# tx.net
KiCad netlist of a schematic drawn in EAGLE
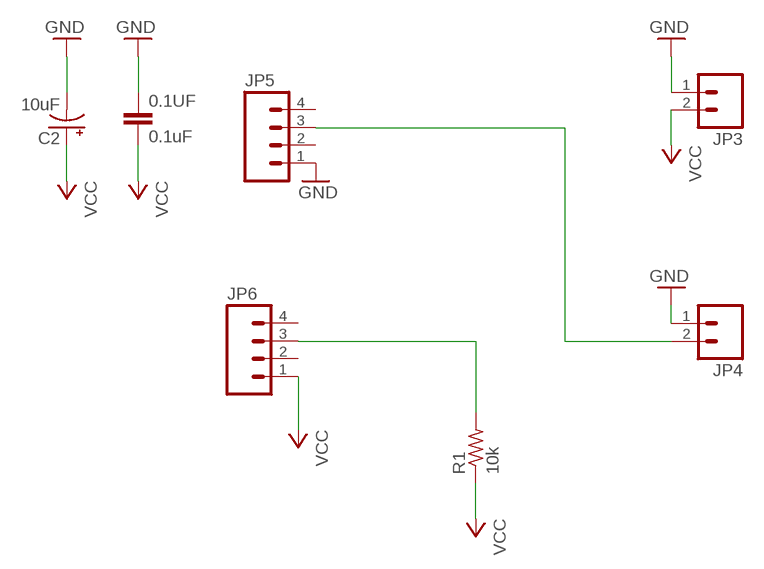
[diagram p0: schematic, sheet 1]

(export (version "E")
  (design (tool "Eeschema 10.0.6"))
  (components
    (comp (ref "0.1UF")
      (value "0.1uF")
      (footprint "eagle-import:0603-CAP")
      (libsource (lib "eagle-import") (part "0.1UF-100V-10%(0603)"))
    )
    (comp (ref "C2")
      (value "10uF")
      (footprint "eagle-import:EIA6032")
      (libsource (lib "eagle-import") (part "CAP_POL6032"))
    )
    (comp (ref "JP3")
      (value "M02PTH")
      (footprint "eagle-import:1X02")
      (libsource (lib "eagle-import") (part "M02PTH"))
    )
    (comp (ref "JP4")
      (value "M02PTH")
      (footprint "eagle-import:1X02")
      (libsource (lib "eagle-import") (part "M02PTH"))
    )
    (comp (ref "JP5")
      (value "M041X04_NO_SILK")
      (footprint "eagle-import:1X04_NO_SILK")
      (libsource (lib "eagle-import") (part "M041X04_NO_SILK"))
    )
    (comp (ref "JP6")
      (value "M041X04_NO_SILK")
      (footprint "eagle-import:1X04_NO_SILK")
      (libsource (lib "eagle-import") (part "M041X04_NO_SILK"))
    )
    (comp (ref "R1")
      (value "10k")
      (footprint "eagle-import:R0805")
      (libsource (lib "eagle-import") (part "R-US_R0805"))
    )
  )
  (nets
    (net (code "1") (name "GND") (class "Default")
      (node (ref "0.1UF") (pin "1") (pinfunction "1_1") (pintype "passive"))
      (node (ref "C2") (pin "P$2") (pinfunction "-_P$2") (pintype "passive"))
      (node (ref "JP3") (pin "1") (pinfunction "1_1") (pintype "passive"))
      (node (ref "JP4") (pin "1") (pinfunction "1_1") (pintype "passive"))
      (node (ref "JP5") (pin "1") (pinfunction "1_1") (pintype "passive"))
    )
    (net (code "2") (name "Net-(JP4-Pad2)") (class "Default")
      (node (ref "JP4") (pin "2") (pinfunction "2_2") (pintype "passive"))
      (node (ref "JP5") (pin "3") (pinfunction "3_3") (pintype "passive"))
    )
    (net (code "3") (name "Net-(JP6-Pad3)") (class "Default")
      (node (ref "JP6") (pin "3") (pinfunction "3_3") (pintype "passive"))
      (node (ref "R1") (pin "2") (pinfunction "2_2") (pintype "passive"))
    )
    (net (code "4") (name "VCC") (class "Default")
      (node (ref "0.1UF") (pin "2") (pinfunction "2_2") (pintype "passive"))
      (node (ref "C2") (pin "P$1") (pinfunction "+_P$1") (pintype "passive"))
      (node (ref "JP3") (pin "2") (pinfunction "2_2") (pintype "passive"))
      (node (ref "JP6") (pin "1") (pinfunction "1_1") (pintype "passive"))
      (node (ref "R1") (pin "1") (pinfunction "1_1") (pintype "passive"))
    )
    (net (code "5") (name "unconnected-(JP5-Pad2)") (class "Default")
      (node (ref "JP5") (pin "2") (pinfunction "2_2") (pintype "passive"))
    )
    (net (code "6") (name "unconnected-(JP5-Pad4)") (class "Default")
      (node (ref "JP5") (pin "4") (pinfunction "4_4") (pintype "passive"))
    )
    (net (code "7") (name "unconnected-(JP6-Pad2)") (class "Default")
      (node (ref "JP6") (pin "2") (pinfunction "2_2") (pintype "passive"))
    )
    (net (code "8") (name "unconnected-(JP6-Pad4)") (class "Default")
      (node (ref "JP6") (pin "4") (pinfunction "4_4") (pintype "passive"))
    )
  )
)
